# IMU.net
KiCad netlist of a schematic drawn in Altium Designer
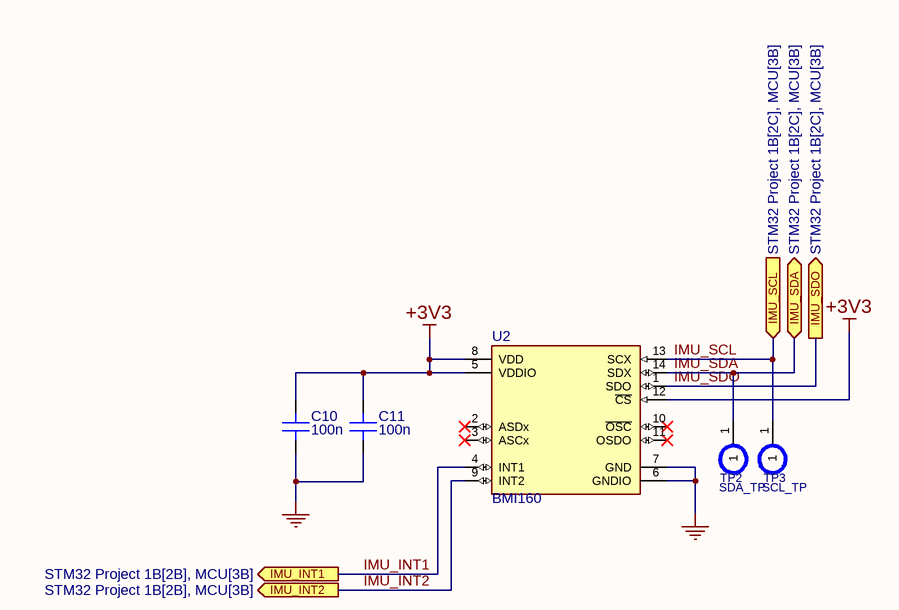
[diagram p0: IMU.SchDoc]

(export (version "E")
  (design (tool "Eeschema 10.0.6"))
  (components
    (comp (ref "C10")
      (value "100n")
      (footprint "CAP_0805")
      (description "Capacitor SMD 0805 Generic")
      (libsource (lib "Generic-Schematic-Library") (part "CAP_0805"))
    )
    (comp (ref "C11")
      (value "100n")
      (footprint "CAP_0805")
      (description "Capacitor SMD 0805 Generic")
      (libsource (lib "Generic-Schematic-Library") (part "CAP_0805"))
    )
    (comp (ref "TP2")
      (value "SDA_TP")
      (footprint "TEST_POINT_SMD")
      (description "Test Point SMD Generic - for in circuit test")
      (libsource (lib "Generic-Schematic-Library") (part "TEST_POINT_SMD"))
    )
    (comp (ref "TP3")
      (value "SCL_TP")
      (footprint "TEST_POINT_SMD")
      (description "Test Point SMD Generic - for in circuit test")
      (libsource (lib "Generic-Schematic-Library") (part "TEST_POINT_SMD"))
    )
    (comp (ref "U2")
      (value "BMI160")
      (footprint "BMI160")
      (description "IMU ACCEL/GYRO I2C/SPI 14LGA")
      (libsource (lib "Generic-Schematic-Library") (part "BMI160"))
    )
  )
  (nets
    (net (code "1") (name "+3V3") (class "Default")
      (node (ref "C10") (pin "2") (pintype "passive"))
      (node (ref "C11") (pin "2") (pintype "passive"))
      (node (ref "U2") (pin "12") (pinfunction "~{CS}_12") (pintype "input"))
      (node (ref "U2") (pin "5") (pinfunction "VDDIO_5") (pintype "power_in"))
      (node (ref "U2") (pin "8") (pinfunction "VDD_8") (pintype "power_in"))
    )
    (net (code "2") (name "/IMU_INT1") (class "Default")
      (node (ref "U2") (pin "4") (pinfunction "INT1_4") (pintype "bidirectional"))
    )
    (net (code "3") (name "/IMU_INT2") (class "Default")
      (node (ref "U2") (pin "9") (pinfunction "INT2_9") (pintype "bidirectional"))
    )
    (net (code "4") (name "/IMU_SCL") (class "Default")
      (node (ref "TP3") (pin "1") (pinfunction "1_1") (pintype "passive"))
      (node (ref "U2") (pin "13") (pinfunction "SCX_13") (pintype "input"))
    )
    (net (code "5") (name "/IMU_SDA") (class "Default")
      (node (ref "TP2") (pin "1") (pinfunction "1_1") (pintype "passive"))
      (node (ref "U2") (pin "14") (pinfunction "SDX_14") (pintype "bidirectional"))
    )
    (net (code "6") (name "/IMU_SDO") (class "Default")
      (node (ref "U2") (pin "1") (pinfunction "SDO_1") (pintype "bidirectional"))
    )
    (net (code "7") (name "GND") (class "Default")
      (node (ref "C10") (pin "1") (pintype "passive"))
      (node (ref "C11") (pin "1") (pintype "passive"))
      (node (ref "U2") (pin "6") (pinfunction "GNDIO_6") (pintype "power_in"))
      (node (ref "U2") (pin "7") (pinfunction "GND_7") (pintype "power_in"))
    )
    (net (code "8") (name "unconnected-(U2-ASCx-Pad3)") (class "Default")
      (node (ref "U2") (pin "3") (pinfunction "ASCx_3") (pintype "bidirectional+no_connect"))
    )
    (net (code "9") (name "unconnected-(U2-ASDx-Pad2)") (class "Default")
      (node (ref "U2") (pin "2") (pinfunction "ASDx_2") (pintype "bidirectional+no_connect"))
    )
    (net (code "10") (name "unconnected-(U2-OSDO-Pad11)") (class "Default")
      (node (ref "U2") (pin "11") (pinfunction "OSDO_11") (pintype "bidirectional+no_connect"))
    )
    (net (code "11") (name "unconnected-(U2-~{OSC}-Pad10)") (class "Default")
      (node (ref "U2") (pin "10") (pinfunction "~{OSC}_10") (pintype "bidirectional+no_connect"))
    )
  )
)
